# Batt_Protection.net
KiCad netlist of a schematic drawn in Altium Designer
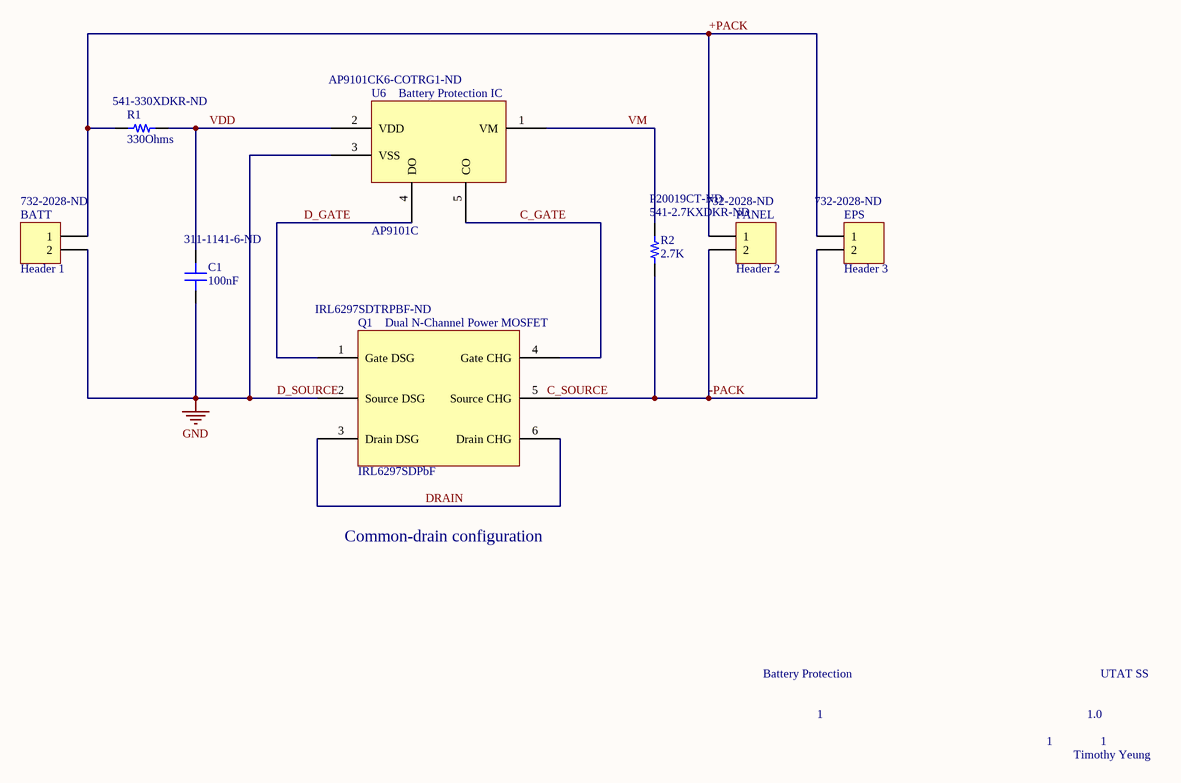
[diagram p0: Batt_Protection.SchDoc]

(export (version "E")
  (design (tool "Eeschema 10.0.6"))
  (components
    (comp (ref "BATT")
      (value "Header 1")
      (footprint "SAM9552-ND")
      (description "Header, 2-Pin")
      (fields
        (field (name "SUPPLIER PART NUMBER 1") "732-2028-ND")
        (field (name "MANUFACTURER") "Wurth Electronics")
        (field (name "MANUFACTURER PART NUMBER") "691102710002")
        (field (name "PUBLISHER") "Altium Limited")
      )
      (libsource (lib "") (part "Header 2_1"))
    )
    (comp (ref "C1")
      (value "100nF")
      (footprint "1608[0603]")
      (description "SMT Capacitor")
      (fields
        (field (name "SUPPLIER PART NUMBER 1") "311-1141-6-ND")
        (field (name "MANUFACTURER") "Yageo")
        (field (name "MANUFACTURER PART NUMBER") "CC0805KRX7R8BB104")
      )
      (libsource (lib "Passives") (part "Capacitor"))
    )
    (comp (ref "EPS")
      (value "Header 3")
      (footprint "CON2_SCREW_5.00MM_691102710002")
      (description "Header, 2-Pin")
      (fields
        (field (name "SUPPLIER PART NUMBER 1") "732-2028-ND")
        (field (name "MANUFACTURER") "Wurth Electronics")
        (field (name "MANUFACTURER PART NUMBER") "691102710002")
        (field (name "PUBLISHER") "Altium Limited")
      )
      (libsource (lib "Miscellaneous Connectors") (part "Header 2"))
    )
    (comp (ref "PANEL")
      (value "Header 2")
      (footprint "CON2_SCREW_5.00MM_691102710002")
      (description "Header, 2-Pin")
      (fields
        (field (name "SUPPLIER PART NUMBER 1") "732-2028-ND")
        (field (name "MANUFACTURER") "Wurth Electronics")
        (field (name "MANUFACTURER PART NUMBER") "691102710002")
        (field (name "PUBLISHER") "Altium Limited")
      )
      (libsource (lib "Miscellaneous Connectors") (part "Header 2"))
    )
    (comp (ref "Q1")
      (value "IRL6297SDPbF")
      (footprint "IRL6297SDPbF")
      (description "Dual N-Channel Power MOSFET")
      (fields
        (field (name "SUPPLIER PART NUMBER 1") "IRL6297SDTRPBF-ND")
        (field (name "MANUFACTURER") "International Rectifier")
        (field (name "MANUFACTURER PART NUMBER") "IRL6297SDTRPBF")
      )
      (libsource (lib "EPS") (part "IRL6297SDPbF"))
    )
    (comp (ref "R1")
      (value "330Ohms")
      (footprint "1608[0603]")
      (description "SMT Resistor")
      (fields
        (field (name "SUPPLIER PART NUMBER 1") "541-330XDKR-ND")
        (field (name "MANUFACTURER") "Vishay Dale")
        (field (name "MANUFACTURER PART NUMBER") "CRCW2512330RJNEG")
      )
      (libsource (lib "Passives") (part "Resistor"))
    )
    (comp (ref "R2")
      (value "2.7K")
      (footprint "1608[0603]")
      (description "SMT Resistor")
      (fields
        (field (name "SUPPLIER PART NUMBER 1") "541-2.7KXDKR-ND")
        (field (name "MANUFACTURER") "Vishay Dale")
        (field (name "MANUFACTURER PART NUMBER") "CRCW25122K70JNEG")
        (field (name "SUPPLIER PART NUMBER 2") "P20019CT-ND")
      )
      (libsource (lib "Passives") (part "Resistor"))
    )
    (comp (ref "U6")
      (value "AP9101C")
      (footprint "AP9101C-776313")
      (description "Battery Protection IC")
      (fields
        (field (name "SUPPLIER PART NUMBER 1") "AP9101CK6-COTRG1-ND")
        (field (name "MANUFACTURER") "Diodes")
        (field (name "MANUFACTURER PART NUMBER") "AP9101CK6-COTRG1")
      )
      (libsource (lib "EPS") (part "AP9101C"))
    )
  )
  (nets
    (net (code "1") (name "/+PACK") (class "Default")
      (node (ref "BATT") (pin "1") (pinfunction "1_1") (pintype "passive"))
      (node (ref "EPS") (pin "1") (pinfunction "1_1") (pintype "passive"))
      (node (ref "PANEL") (pin "1") (pinfunction "1_1") (pintype "passive"))
      (node (ref "R1") (pin "1") (pinfunction "1_1") (pintype "passive"))
    )
    (net (code "2") (name "/-PACK") (class "Default")
      (node (ref "EPS") (pin "2") (pinfunction "2_2") (pintype "passive"))
      (node (ref "PANEL") (pin "2") (pinfunction "2_2") (pintype "passive"))
      (node (ref "Q1") (pin "5") (pinfunction "Source_CHG_5") (pintype "passive"))
      (node (ref "R2") (pin "1") (pinfunction "1_1") (pintype "passive"))
    )
    (net (code "3") (name "/C_GATE") (class "Default")
      (node (ref "Q1") (pin "4") (pinfunction "Gate_CHG_4") (pintype "passive"))
      (node (ref "U6") (pin "5") (pinfunction "CO_5") (pintype "passive"))
    )
    (net (code "5") (name "/DRAIN") (class "Default")
      (node (ref "Q1") (pin "3") (pinfunction "Drain_DSG_3") (pintype "passive"))
      (node (ref "Q1") (pin "6") (pinfunction "Drain_CHG_6") (pintype "passive"))
    )
    (net (code "6") (name "/D_GATE") (class "Default")
      (node (ref "Q1") (pin "1") (pinfunction "Gate_DSG_1") (pintype "passive"))
      (node (ref "U6") (pin "4") (pinfunction "DO_4") (pintype "passive"))
    )
    (net (code "7") (name "/VDD") (class "Default")
      (node (ref "C1") (pin "2") (pinfunction "2_2") (pintype "passive"))
      (node (ref "R1") (pin "2") (pinfunction "2_2") (pintype "passive"))
      (node (ref "U6") (pin "2") (pinfunction "VDD_2") (pintype "passive"))
    )
    (net (code "8") (name "/VM") (class "Default")
      (node (ref "R2") (pin "2") (pinfunction "2_2") (pintype "passive"))
      (node (ref "U6") (pin "1") (pinfunction "VM_1") (pintype "passive"))
    )
    (net (code "9") (name "GND") (class "Default")
      (node (ref "BATT") (pin "2") (pinfunction "2_2") (pintype "passive"))
      (node (ref "C1") (pin "1") (pinfunction "1_1") (pintype "passive"))
      (node (ref "Q1") (pin "2") (pinfunction "Source_DSG_2") (pintype "passive"))
      (node (ref "U6") (pin "3") (pinfunction "VSS_3") (pintype "passive"))
    )
  )
)
